# PWR_MGMT.net
KiCad netlist of a schematic drawn in Altium Designer
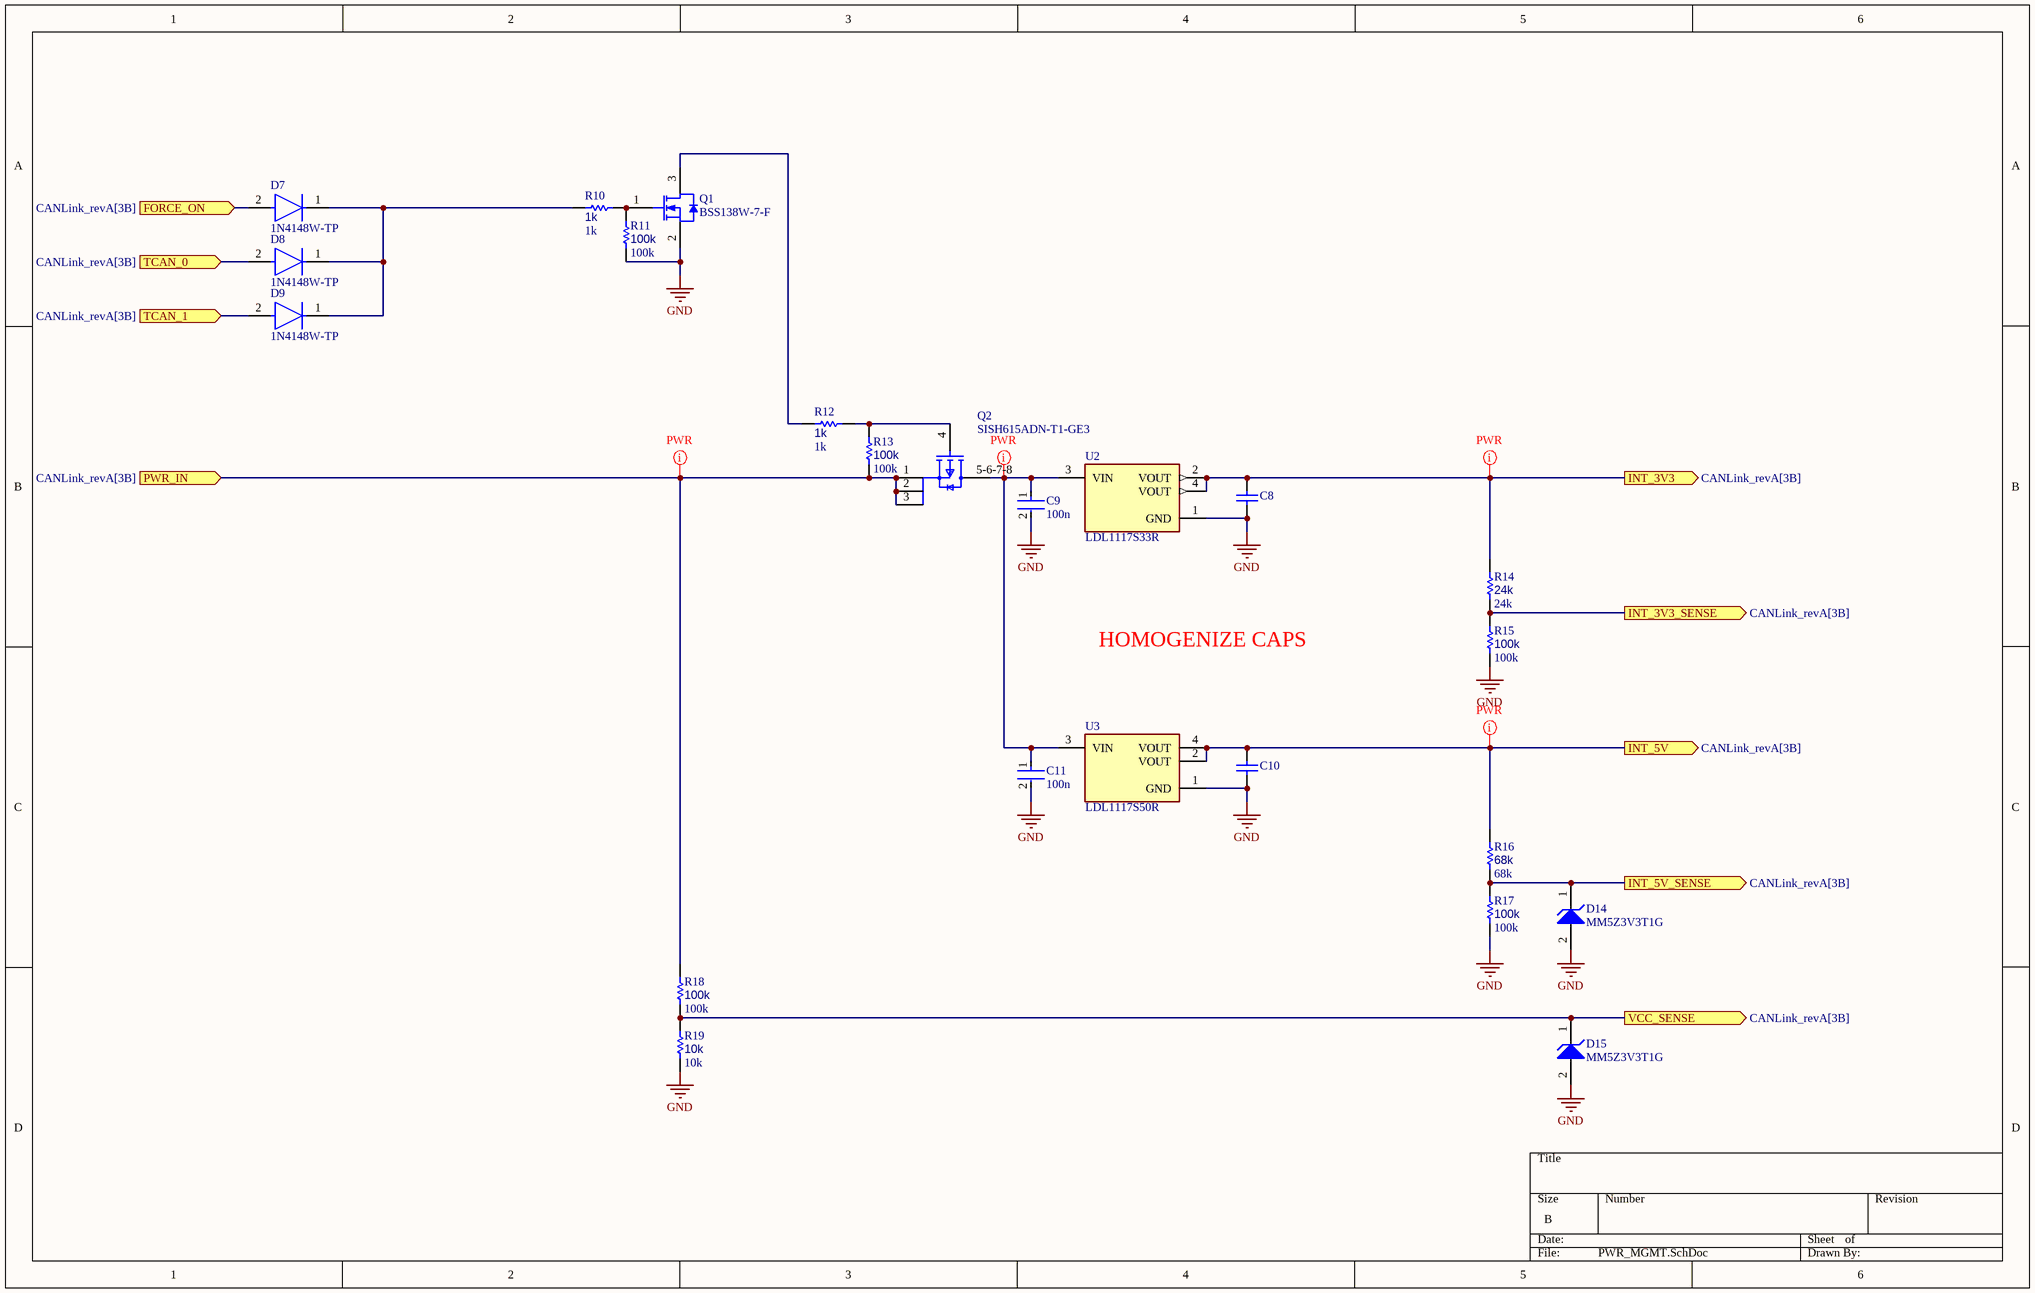
[diagram p0: PWR_MGMT.SchDoc]

(export (version "E")
  (design (tool "Eeschema 10.0.6"))
  (components
    (comp (ref "C8")
      (value "0805ZG106ZAT2A")
      (footprint "CAPC2013X152X50NL20T25")
      (fields (field (name "MANUFACTURER") "AVX Interconnect / Elco"))
      (libsource (lib "Altium Content Vault") (part "CAP"))
    )
    (comp (ref "C9")
      (value "100n")
      (footprint "FP-0402-L_1_0_0_05-W_0_5-IPC_A")
      (description "LARGE PADS, 0402 CAP, CHANGE COMMENT TO MATCH REAL P/N")
      (libsource (lib "Space Concordia") (part "b4654b650e69147ec39a6b967a45e02"))
    )
    (comp (ref "C10")
      (value "0805ZG106ZAT2A")
      (footprint "CAPC2013X152X50NL20T25")
      (fields (field (name "MANUFACTURER") "AVX Interconnect / Elco"))
      (libsource (lib "Altium Content Vault") (part "CAP"))
    )
    (comp (ref "C11")
      (value "100n")
      (footprint "FP-0402-L_1_0_0_05-W_0_5-IPC_A")
      (description "LARGE PADS, 0402 CAP, CHANGE COMMENT TO MATCH REAL P/N")
      (libsource (lib "Space Concordia") (part "b4654b650e69147ec39a6b967a45e02"))
    )
    (comp (ref "D7")
      (value "1N4148W-TP")
      (footprint "FP-SOD-123-IPC_A")
      (description "DIODE GEN PURP 100V 150MA SOD123")
      (libsource (lib "Altium Content Vault") (part "d7152d700b627762746794eb795d46e"))
    )
    (comp (ref "D8")
      (value "1N4148W-TP")
      (footprint "FP-SOD-123-IPC_A")
      (description "DIODE GEN PURP 100V 150MA SOD123")
      (libsource (lib "Altium Content Vault") (part "d7152d700b627762746794eb795d46e"))
    )
    (comp (ref "D9")
      (value "1N4148W-TP")
      (footprint "FP-SOD-123-IPC_A")
      (description "DIODE GEN PURP 100V 150MA SOD123")
      (libsource (lib "Altium Content Vault") (part "d7152d700b627762746794eb795d46e"))
    )
    (comp (ref "D14")
      (value "MM5Z3V3T1G")
      (footprint "ONSC-SOD-523-2-502-01_V")
      (description "Zener Voltage Regulator, 500 mW, 2-Pin SOD-523, Pb-Free, Tape and Reel")
      (fields (field (name "MANUFACTURER") "On Semiconductor"))
      (libsource (lib "Altium Content Vault") (part "ONSC-K1A2-2"))
    )
    (comp (ref "D15")
      (value "MM5Z3V3T1G")
      (footprint "ONSC-SOD-523-2-502-01_V")
      (description "Zener Voltage Regulator, 500 mW, 2-Pin SOD-523, Pb-Free, Tape and Reel")
      (fields (field (name "MANUFACTURER") "On Semiconductor"))
      (libsource (lib "Altium Content Vault") (part "ONSC-K1A2-2"))
    )
    (comp (ref "Q1")
      (value "BSS138W-7-F")
      (footprint "DIOD-SOT323-3_V")
      (fields (field (name "MANUFACTURER") "DiodesIncorporated"))
      (libsource (lib "Altium Content Vault") (part "NEMOS-GSD-3"))
    )
    (comp (ref "Q2")
      (value "SISH615ADN-T1-GE3")
      (footprint "SISH615ADN-T1-GE3-Footprint-1")
      (description "Trans MOSFET P-CH 20V 22.1A 8-Pin PowerPAK 1212 EP T/R")
      (libsource (lib "Space Concordia") (part "CMP-013-00036-4"))
    )
    (comp (ref "R10")
      (value "1k")
      (footprint "R0603B")
      (description "Resistor")
      (fields (field (name "ALTIUM_VALUE") "1k"))
      (libsource (lib "Space Concordia") (part "Resistor"))
    )
    (comp (ref "R11")
      (value "100k")
      (footprint "R0603B")
      (description "Resistor")
      (fields (field (name "ALTIUM_VALUE") "100k"))
      (libsource (lib "Space Concordia") (part "Resistor"))
    )
    (comp (ref "R12")
      (value "1k")
      (footprint "R0603B")
      (description "Resistor")
      (fields (field (name "ALTIUM_VALUE") "1k"))
      (libsource (lib "Space Concordia") (part "Resistor"))
    )
    (comp (ref "R13")
      (value "100k")
      (footprint "R0603B")
      (description "Resistor")
      (fields (field (name "ALTIUM_VALUE") "100k"))
      (libsource (lib "Space Concordia") (part "Resistor"))
    )
    (comp (ref "R14")
      (value "24k")
      (footprint "R0603B")
      (description "Resistor")
      (fields (field (name "ALTIUM_VALUE") "24k"))
      (libsource (lib "Space Concordia") (part "Resistor"))
    )
    (comp (ref "R15")
      (value "100k")
      (footprint "R0603B")
      (description "Resistor")
      (fields (field (name "ALTIUM_VALUE") "100k"))
      (libsource (lib "Space Concordia") (part "Resistor"))
    )
    (comp (ref "R16")
      (value "68k")
      (footprint "R0603B")
      (description "Resistor")
      (fields (field (name "ALTIUM_VALUE") "68k"))
      (libsource (lib "Space Concordia") (part "Resistor"))
    )
    (comp (ref "R17")
      (value "100k")
      (footprint "R0603B")
      (description "Resistor")
      (fields (field (name "ALTIUM_VALUE") "100k"))
      (libsource (lib "Space Concordia") (part "Resistor"))
    )
    (comp (ref "R18")
      (value "100k")
      (footprint "R0603B")
      (description "Resistor")
      (fields (field (name "ALTIUM_VALUE") "100k"))
      (libsource (lib "Space Concordia") (part "Resistor"))
    )
    (comp (ref "R19")
      (value "10k")
      (footprint "R0603B")
      (description "Resistor")
      (fields (field (name "ALTIUM_VALUE") "10k"))
      (libsource (lib "Space Concordia") (part "Resistor"))
    )
    (comp (ref "U2")
      (value "LDL1117S33R")
      (footprint "FP-SOT223-0046067-IPC_C")
      (description "IC REG LINEAR 3.3V 1.2A SOT223")
      (fields
        (field (name "OCTOPART") "https://octopart.com/ldl1117s33r-stmicroelectronics-81876163")
        (field (name "MANUFACTURER") "STMicroelectronics")
      )
      (libsource (lib "Altium Content Vault") (part "a602d55cb6d43002de8a72f1c695f0a"))
    )
    (comp (ref "U3")
      (value "LDL1117S50R")
      (footprint "FP-SOT-223-0046067_14-MFG")
      (description "IC REG LINEAR 5V 1.2A SOT223")
      (fields
        (field (name "OCTOPART") "https://octopart.com/ldl1117s50r-stmicroelectronics-81876164")
        (field (name "MANUFACTURER") "STMicroelectronics")
      )
      (libsource (lib "Altium Content Vault") (part "a368f1d72361ca9956852d636243424"))
    )
  )
  (nets
    (net (code "1") (name "/FORCE_ON") (class "Default")
      (node (ref "D7") (pin "2") (pinfunction "A_2") (pintype "passive"))
    )
    (net (code "2") (name "/INT_3V3") (class "Default")
      (node (ref "C8") (pin "2") (pinfunction "2_2") (pintype "passive"))
      (node (ref "R14") (pin "1") (pinfunction "1_1") (pintype "passive"))
      (node (ref "U2") (pin "2") (pinfunction "VOUT_2") (pintype "output"))
      (node (ref "U2") (pin "4") (pinfunction "VOUT_4") (pintype "output"))
    )
    (net (code "3") (name "/INT_3V3_SENSE") (class "Default")
      (node (ref "R14") (pin "2") (pinfunction "2_2") (pintype "passive"))
      (node (ref "R15") (pin "1") (pinfunction "1_1") (pintype "passive"))
    )
    (net (code "4") (name "/INT_5V") (class "Default")
      (node (ref "C10") (pin "2") (pinfunction "2_2") (pintype "passive"))
      (node (ref "R16") (pin "1") (pinfunction "1_1") (pintype "passive"))
      (node (ref "U3") (pin "2") (pinfunction "VOUT_2") (pintype "power_in"))
      (node (ref "U3") (pin "4") (pinfunction "VOUT_4") (pintype "power_in"))
    )
    (net (code "5") (name "/INT_5V_SENSE") (class "Default")
      (node (ref "D14") (pin "1") (pinfunction "K_1") (pintype "passive"))
      (node (ref "R16") (pin "2") (pinfunction "2_2") (pintype "passive"))
      (node (ref "R17") (pin "1") (pinfunction "1_1") (pintype "passive"))
    )
    (net (code "6") (name "/PWR_IN") (class "Default")
      (node (ref "Q2") (pin "1") (pinfunction "S_1") (pintype "passive"))
      (node (ref "Q2") (pin "2") (pinfunction "S_2") (pintype "passive"))
      (node (ref "Q2") (pin "3") (pinfunction "S_3") (pintype "passive"))
      (node (ref "R13") (pin "2") (pinfunction "2_2") (pintype "passive"))
      (node (ref "R18") (pin "1") (pinfunction "1_1") (pintype "passive"))
    )
    (net (code "7") (name "/TCAN_0") (class "Default")
      (node (ref "D8") (pin "2") (pinfunction "A_2") (pintype "passive"))
    )
    (net (code "8") (name "/TCAN_1") (class "Default")
      (node (ref "D9") (pin "2") (pinfunction "A_2") (pintype "passive"))
    )
    (net (code "9") (name "/VCC_SENSE") (class "Default")
      (node (ref "D15") (pin "1") (pinfunction "K_1") (pintype "passive"))
      (node (ref "R18") (pin "2") (pinfunction "2_2") (pintype "passive"))
      (node (ref "R19") (pin "1") (pinfunction "1_1") (pintype "passive"))
    )
    (net (code "10") (name "GND") (class "Default")
      (node (ref "C10") (pin "1") (pinfunction "1_1") (pintype "passive"))
      (node (ref "C11") (pin "2") (pinfunction "2_2") (pintype "passive"))
      (node (ref "C8") (pin "1") (pinfunction "1_1") (pintype "passive"))
      (node (ref "C9") (pin "2") (pinfunction "2_2") (pintype "passive"))
      (node (ref "D14") (pin "2") (pinfunction "A_2") (pintype "passive"))
      (node (ref "D15") (pin "2") (pinfunction "A_2") (pintype "passive"))
      (node (ref "Q1") (pin "2") (pinfunction "S_2") (pintype "passive"))
      (node (ref "R11") (pin "2") (pinfunction "2_2") (pintype "passive"))
      (node (ref "R15") (pin "2") (pinfunction "2_2") (pintype "passive"))
      (node (ref "R17") (pin "2") (pinfunction "2_2") (pintype "passive"))
      (node (ref "R19") (pin "2") (pinfunction "2_2") (pintype "passive"))
      (node (ref "U2") (pin "1") (pinfunction "GND_1") (pintype "power_in"))
      (node (ref "U3") (pin "1") (pinfunction "GND_1") (pintype "power_in"))
    )
    (net (code "11") (name "Net-(D7-C)") (class "Default")
      (node (ref "D7") (pin "1") (pinfunction "C_1") (pintype "passive"))
      (node (ref "D8") (pin "1") (pinfunction "C_1") (pintype "passive"))
      (node (ref "D9") (pin "1") (pinfunction "C_1") (pintype "passive"))
      (node (ref "R10") (pin "2") (pinfunction "2_2") (pintype "passive"))
    )
    (net (code "12") (name "Net-(Q1-D)") (class "Default")
      (node (ref "Q1") (pin "3") (pinfunction "D_3") (pintype "passive"))
      (node (ref "R12") (pin "2") (pinfunction "2_2") (pintype "passive"))
    )
    (net (code "13") (name "Net-(Q1-G)") (class "Default")
      (node (ref "Q1") (pin "1") (pinfunction "G_1") (pintype "passive"))
      (node (ref "R10") (pin "1") (pinfunction "1_1") (pintype "passive"))
      (node (ref "R11") (pin "1") (pinfunction "1_1") (pintype "passive"))
    )
    (net (code "14") (name "Net-(Q2-D)") (class "Default")
      (node (ref "C11") (pin "1") (pinfunction "1_1") (pintype "passive"))
      (node (ref "C9") (pin "1") (pinfunction "1_1") (pintype "passive"))
      (node (ref "Q2") (pin "5-6-7-8") (pinfunction "D_5-6-7-8") (pintype "passive"))
      (node (ref "U2") (pin "3") (pinfunction "VIN_3") (pintype "power_in"))
      (node (ref "U3") (pin "3") (pinfunction "VIN_3") (pintype "power_in"))
    )
    (net (code "15") (name "Net-(Q2-G)") (class "Default")
      (node (ref "Q2") (pin "4") (pinfunction "G_4") (pintype "passive"))
      (node (ref "R12") (pin "1") (pinfunction "1_1") (pintype "passive"))
      (node (ref "R13") (pin "1") (pinfunction "1_1") (pintype "passive"))
    )
  )
)
